# L_Subsys1.net
KiCad netlist of a schematic drawn in Altium Designer
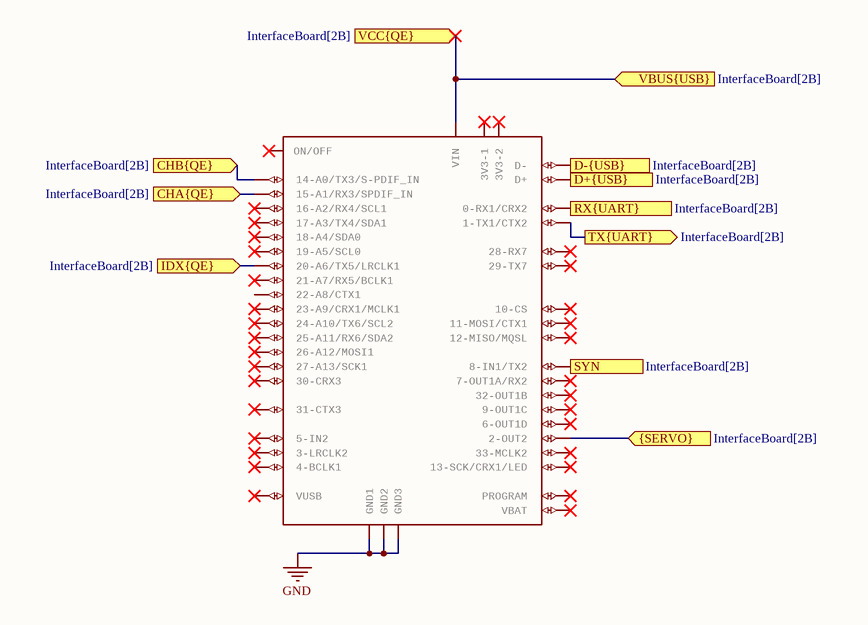
[diagram p0: L Subsys1.SchDoc]

(export (version "E")
  (design (tool "Eeschema 10.0.6"))
  (components
    (comp (ref "UL")
      (value "DEV-16771")
      (footprint "TEENSY40")
      (libsource (lib "TEENSYV1.Library") (part "TEENSY40"))
    )
  )
  (nets
    (net (code "10") (name "/CHA{QE}") (class "Default")
      (node (ref "UL") (pin "15-A1/RX3/S-PDIF_IN") (pinfunction "15-A1/RX3/SPDIF_IN_15-A1/RX3/S-PDIF_IN") (pintype "bidirectional"))
    )
    (net (code "11") (name "/CHB{QE}") (class "Default")
      (node (ref "UL") (pin "14-A0/TX3/S-PFI_OUT") (pinfunction "14-A0/TX3/S-PDIF_IN_14-A0/TX3/S-PFI_OUT") (pintype "bidirectional"))
    )
    (net (code "12") (name "/D+{USB}") (class "Default")
      (node (ref "UL") (pin "D+") (pinfunction "D+_D+") (pintype "bidirectional"))
    )
    (net (code "13") (name "/D-{USB}") (class "Default")
      (node (ref "UL") (pin "D-") (pinfunction "D-_D-") (pintype "bidirectional"))
    )
    (net (code "14") (name "/IDX{QE}") (class "Default")
      (node (ref "UL") (pin "20-A6/TX5/LRCLK1") (pinfunction "20-A6/TX5/LRCLK1_20-A6/TX5/LRCLK1") (pintype "bidirectional"))
    )
    (net (code "15") (name "/RX{UART}") (class "Default")
      (node (ref "UL") (pin "0-RX1") (pinfunction "0-RX1/CRX2_0-RX1") (pintype "bidirectional"))
    )
    (net (code "16") (name "/SYN") (class "Default")
      (node (ref "UL") (pin "8-TX2/IN1") (pinfunction "8-IN1/TX2_8-TX2/IN1") (pintype "bidirectional"))
    )
    (net (code "17") (name "/TX{UART}") (class "Default")
      (node (ref "UL") (pin "1-TX1") (pinfunction "1-TX1/CTX2_1-TX1") (pintype "bidirectional"))
    )
    (net (code "18") (name "/VBUS{USB}") (class "Default")
      (node (ref "UL") (pin "VIN") (pinfunction "VIN_VIN") (pintype "bidirectional+no_connect"))
    )
    (net (code "19") (name "/{SERVO}") (class "Default")
      (node (ref "UL") (pin "2-OUT2") (pinfunction "2-OUT2_2-OUT2") (pintype "bidirectional"))
    )
    (net (code "20") (name "GND") (class "Default")
      (node (ref "UL") (pin "GND1") (pinfunction "GND1_GND1") (pintype "bidirectional"))
      (node (ref "UL") (pin "GND2") (pinfunction "GND2_GND2") (pintype "bidirectional"))
      (node (ref "UL") (pin "GND3") (pinfunction "GND3_GND3") (pintype "bidirectional"))
    )
    (net (code "21") (name "unconnected-(UL-4-BCLK1-Pad4-BCLK2)") (class "Default")
      (node (ref "UL") (pin "4-BCLK2") (pinfunction "4-BCLK1_4-BCLK2") (pintype "bidirectional+no_connect"))
    )
    (net (code "22") (name "unconnected-(UL-7-OUT1A{slash}RX2-Pad7-RX2{slash}OUT1A)") (class "Default")
      (node (ref "UL") (pin "7-RX2/OUT1A") (pinfunction "7-OUT1A/RX2_7-RX2/OUT1A") (pintype "bidirectional+no_connect"))
    )
    (net (code "23") (name "unconnected-(UL-10-CS-Pad10-CS{slash}MQSR)") (class "Default")
      (node (ref "UL") (pin "10-CS/MQSR") (pinfunction "10-CS_10-CS/MQSR") (pintype "bidirectional+no_connect"))
    )
    (net (code "24") (name "unconnected-(UL-12-MISO{slash}MQSL-Pad12-MIO{slash}MQSL)") (class "Default")
      (node (ref "UL") (pin "12-MIO/MQSL") (pinfunction "12-MISO/MQSL_12-MIO/MQSL") (pintype "bidirectional+no_connect"))
    )
    (net (code "25") (name "unconnected-(UL-23-A9{slash}CRX1{slash}MCLK1-Pad23-A9{slash}CRX1{slash}CCLK1)") (class "Default")
      (node (ref "UL") (pin "23-A9/CRX1/CCLK1") (pinfunction "23-A9/CRX1/MCLK1_23-A9/CRX1/CCLK1") (pintype "bidirectional+no_connect"))
    )
    (net (code "26") (name "unconnected-(UL-25-A11{slash}RX6{slash}SDA2-Pad25-A11{slash}SDA2)") (class "Default")
      (node (ref "UL") (pin "25-A11/SDA2") (pinfunction "25-A11/RX6/SDA2_25-A11/SDA2") (pintype "bidirectional+no_connect"))
    )
    (net (code "27") (name "unconnected-(UL-32-OUT1B-Pad32-OUTB1)") (class "Default")
      (node (ref "UL") (pin "32-OUTB1") (pinfunction "32-OUT1B_32-OUTB1") (pintype "bidirectional+no_connect"))
    )
    (net (code "28") (name "unconnected-(UL-Pad3-LRCLK2)") (class "Default")
      (node (ref "UL") (pin "3-LRCLK2") (pinfunction "3-LRCLK2_3-LRCLK2") (pintype "bidirectional+no_connect"))
    )
    (net (code "29") (name "unconnected-(UL-Pad3V3-1)") (class "Default")
      (node (ref "UL") (pin "3V3-1") (pinfunction "3V3-1_3V3-1") (pintype "bidirectional+no_connect"))
    )
    (net (code "30") (name "unconnected-(UL-Pad3V3-2)") (class "Default")
      (node (ref "UL") (pin "3V3-2") (pinfunction "3V3-2_3V3-2") (pintype "bidirectional+no_connect"))
    )
    (net (code "31") (name "unconnected-(UL-Pad5-IN2)") (class "Default")
      (node (ref "UL") (pin "5-IN2") (pinfunction "5-IN2_5-IN2") (pintype "bidirectional+no_connect"))
    )
    (net (code "32") (name "unconnected-(UL-Pad6-OUT1D)") (class "Default")
      (node (ref "UL") (pin "6-OUT1D") (pinfunction "6-OUT1D_6-OUT1D") (pintype "bidirectional+no_connect"))
    )
    (net (code "33") (name "unconnected-(UL-Pad9-OUT1C)") (class "Default")
      (node (ref "UL") (pin "9-OUT1C") (pinfunction "9-OUT1C_9-OUT1C") (pintype "bidirectional+no_connect"))
    )
    (net (code "34") (name "unconnected-(UL-Pad11-MOSI{slash}CTX1)") (class "Default")
      (node (ref "UL") (pin "11-MOSI/CTX1") (pinfunction "11-MOSI/CTX1_11-MOSI/CTX1") (pintype "bidirectional+no_connect"))
    )
    (net (code "35") (name "unconnected-(UL-Pad13-SCK{slash}CRX1{slash}LED)") (class "Default")
      (node (ref "UL") (pin "13-SCK/CRX1/LED") (pinfunction "13-SCK/CRX1/LED_13-SCK/CRX1/LED") (pintype "bidirectional+no_connect"))
    )
    (net (code "36") (name "unconnected-(UL-Pad16-A2{slash}RX4{slash}SCL1)") (class "Default")
      (node (ref "UL") (pin "16-A2/RX4/SCL1") (pinfunction "16-A2/RX4/SCL1_16-A2/RX4/SCL1") (pintype "bidirectional+no_connect"))
    )
    (net (code "37") (name "unconnected-(UL-Pad17-A3{slash}TX4{slash}SDA1)") (class "Default")
      (node (ref "UL") (pin "17-A3/TX4/SDA1") (pinfunction "17-A3/TX4/SDA1_17-A3/TX4/SDA1") (pintype "bidirectional+no_connect"))
    )
    (net (code "38") (name "unconnected-(UL-Pad18-A4{slash}SDA0)") (class "Default")
      (node (ref "UL") (pin "18-A4/SDA0") (pinfunction "18-A4/SDA0_18-A4/SDA0") (pintype "bidirectional+no_connect"))
    )
    (net (code "39") (name "unconnected-(UL-Pad19-A5{slash}SCL0)") (class "Default")
      (node (ref "UL") (pin "19-A5/SCL0") (pinfunction "19-A5/SCL0_19-A5/SCL0") (pintype "bidirectional+no_connect"))
    )
    (net (code "40") (name "unconnected-(UL-Pad21-A7{slash}RX5{slash}BCLK1)") (class "Default")
      (node (ref "UL") (pin "21-A7/RX5/BCLK1") (pinfunction "21-A7/RX5/BCLK1_21-A7/RX5/BCLK1") (pintype "bidirectional+no_connect"))
    )
    (net (code "41") (name "unconnected-(UL-Pad22-A8{slash}CTX1)") (class "Default")
      (node (ref "UL") (pin "22-A8/CTX1") (pinfunction "22-A8/CTX1_22-A8/CTX1") (pintype "bidirectional"))
    )
    (net (code "42") (name "unconnected-(UL-Pad24-A10{slash}TX6{slash}SCL2)") (class "Default")
      (node (ref "UL") (pin "24-A10/TX6/SCL2") (pinfunction "24-A10/TX6/SCL2_24-A10/TX6/SCL2") (pintype "bidirectional+no_connect"))
    )
    (net (code "43") (name "unconnected-(UL-Pad26-A12{slash}MOSI1)") (class "Default")
      (node (ref "UL") (pin "26-A12/MOSI1") (pinfunction "26-A12/MOSI1_26-A12/MOSI1") (pintype "bidirectional+no_connect"))
    )
    (net (code "44") (name "unconnected-(UL-Pad27-A13{slash}SCK1)") (class "Default")
      (node (ref "UL") (pin "27-A13/SCK1") (pinfunction "27-A13/SCK1_27-A13/SCK1") (pintype "bidirectional+no_connect"))
    )
    (net (code "45") (name "unconnected-(UL-Pad28-RX7)") (class "Default")
      (node (ref "UL") (pin "28-RX7") (pinfunction "28-RX7_28-RX7") (pintype "bidirectional+no_connect"))
    )
    (net (code "46") (name "unconnected-(UL-Pad29-TX7)") (class "Default")
      (node (ref "UL") (pin "29-TX7") (pinfunction "29-TX7_29-TX7") (pintype "bidirectional+no_connect"))
    )
    (net (code "47") (name "unconnected-(UL-Pad30-CRX3)") (class "Default")
      (node (ref "UL") (pin "30-CRX3") (pinfunction "30-CRX3_30-CRX3") (pintype "bidirectional+no_connect"))
    )
    (net (code "48") (name "unconnected-(UL-Pad31-CTX3)") (class "Default")
      (node (ref "UL") (pin "31-CTX3") (pinfunction "31-CTX3_31-CTX3") (pintype "bidirectional+no_connect"))
    )
    (net (code "49") (name "unconnected-(UL-Pad33-MCLK2)") (class "Default")
      (node (ref "UL") (pin "33-MCLK2") (pinfunction "33-MCLK2_33-MCLK2") (pintype "bidirectional+no_connect"))
    )
    (net (code "50") (name "unconnected-(UL-PadON{slash}OFF)") (class "Default")
      (node (ref "UL") (pin "ON/OFF") (pinfunction "ON/OFF_ON/OFF") (pintype "bidirectional+no_connect"))
    )
    (net (code "51") (name "unconnected-(UL-PadPROGRAM)") (class "Default")
      (node (ref "UL") (pin "PROGRAM") (pinfunction "PROGRAM_PROGRAM") (pintype "bidirectional+no_connect"))
    )
    (net (code "52") (name "unconnected-(UL-PadVBAT)") (class "Default")
      (node (ref "UL") (pin "VBAT") (pinfunction "VBAT_VBAT") (pintype "bidirectional+no_connect"))
    )
    (net (code "53") (name "unconnected-(UL-PadVUSB)") (class "Default")
      (node (ref "UL") (pin "VUSB") (pinfunction "VUSB_VUSB") (pintype "bidirectional+no_connect"))
    )
  )
)
